# Main_Board_Guitar_Buffer.net
KiCad netlist of a schematic drawn in Altium Designer
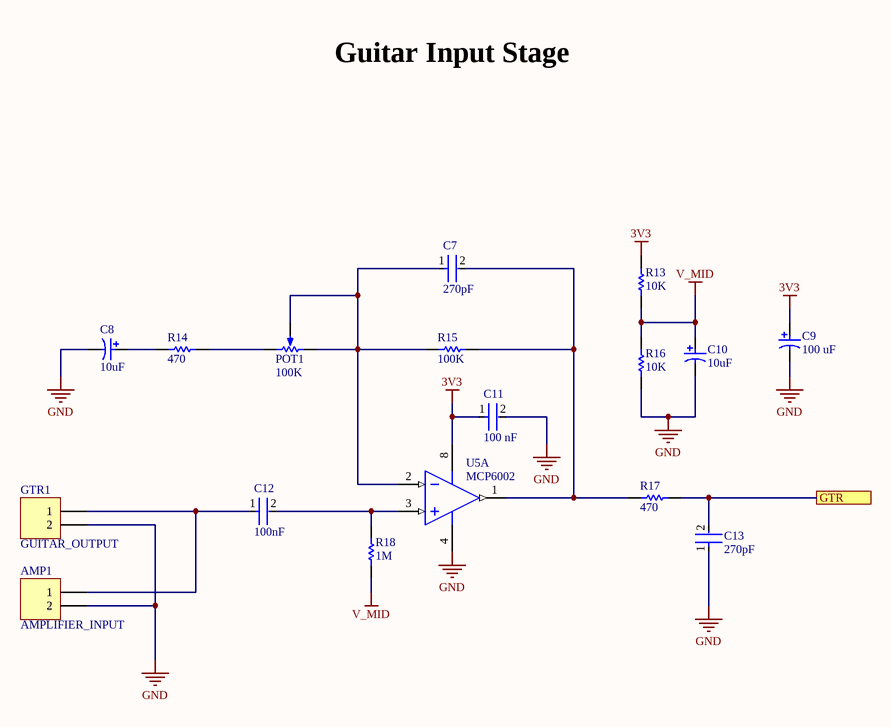
[diagram p0: Main_Board_Guitar_Buffer.SchDoc]

(export (version "E")
  (design (tool "Eeschema 10.0.6"))
  (components
    (comp (ref "AMP1")
      (value "AMPLIFIER_INPUT")
      (footprint "HDR1X2")
      (description "Header, 2-Pin")
      (fields (field (name "PUBLISHER") "Altium Limited"))
      (libsource (lib "Miscellaneous Connectors") (part "Header 2"))
    )
    (comp (ref "C7")
      (value "270pF")
      (footprint "FP-C0805C-DN-MFG")
      (description "CAP CER 270PF 50V C0G/NP0 0805")
      (fields
        (field (name "MANUFACTURER") "KEMET")
        (field (name "MANUFACTURER PART NUMBER") "C0805C271J5GACTU")
      )
      (libsource (lib "Altium Content Vault") (part "b4654b650e69147ec39a6b967a45e02"))
    )
    (comp (ref "C8")
      (value "10uF")
      (footprint "KEMT-A-3216-18-2_M")
      (description "Capacitor, Tantalum, 10 uF, +/- 10%, 10 V, -55 to 125 degC, 2-Pin SMD (1206), RoHS, Tape and Reel")
      (fields (field (name "TOLERANCE") "±10%") (field (name "MANUFACTURER") "Kemet"))
      (libsource (lib "Altium Content Vault") (part "CAP-P-2"))
    )
    (comp (ref "C9")
      (value "100 uF")
      (footprint "KEMT-T491-D_L")
      (fields
        (field (name "MANUFACTURER") "Kemet")
        (field (name "VOLTAGE") "16V")
        (field (name "TOLERANCE") "10%")
      )
      (libsource (lib "Altium Content Vault") (part "CAP-P-2"))
    )
    (comp (ref "C10")
      (value "10uF")
      (footprint "KEMT-A-3216-18-2_M")
      (description "Capacitor, Tantalum, 10 uF, +/- 10%, 10 V, -55 to 125 degC, 2-Pin SMD (1206), RoHS, Tape and Reel")
      (fields (field (name "TOLERANCE") "±10%") (field (name "MANUFACTURER") "Kemet"))
      (libsource (lib "Altium Content Vault") (part "CAP-P-2"))
    )
    (comp (ref "C11")
      (value "100 nF")
      (footprint "FP-C0805C-DN-MFG")
      (description "CAP CER 0.1UF 50V X7R 0805")
      (fields
        (field (name "MANUFACTURER PART NUMBER") "C0805C104K5RACTU")
        (field (name "MANUFACTURER") "KEMET")
      )
      (libsource (lib "Altium Content Vault") (part "b4654b650e69147ec39a6b967a45e02"))
    )
    (comp (ref "C12")
      (value "100nF")
      (footprint "FP-C0805C-DN-MFG")
      (description "CAP CER 0.1UF 50V X7R 0805")
      (fields
        (field (name "MANUFACTURER PART NUMBER") "C0805C104K5RACTU")
        (field (name "MANUFACTURER") "KEMET")
      )
      (libsource (lib "Altium Content Vault") (part "b4654b650e69147ec39a6b967a45e02"))
    )
    (comp (ref "C13")
      (value "270pF")
      (footprint "FP-C0805C-DN-MFG")
      (description "CAP CER 270PF 50V C0G/NP0 0805")
      (fields
        (field (name "MANUFACTURER") "KEMET")
        (field (name "MANUFACTURER PART NUMBER") "C0805C271J5GACTU")
      )
      (libsource (lib "Altium Content Vault") (part "b4654b650e69147ec39a6b967a45e02"))
    )
    (comp (ref "GTR1")
      (value "GUITAR_OUTPUT")
      (footprint "HDR1X2")
      (description "Header, 2-Pin")
      (fields (field (name "PUBLISHER") "Altium Limited"))
      (libsource (lib "Miscellaneous Connectors") (part "Header 2"))
    )
    (comp (ref "POT1")
      (value "100K")
      (footprint "BOUR-3362P")
      (description "Square Trimpot(R) Trimming Potentiometer, 100 KOhm, 300 V, -55 to 125 degC, 3-Pin THD, RoHS, Tube")
      (fields (field (name "TOLERANCE") "1%"))
      (libsource (lib "Altium Content Vault") (part "RES-POT-3"))
    )
    (comp (ref "R13")
      (value "10K")
      (footprint "RESC2013X60X35NL10T20")
      (description "Chip Resistor, 10 KOhm, +/- 1%, 0.125 W, -55 to 155 degC, 0805 (2012 Metric), RoHS, Tape and Reel")
      (fields (field (name "MANUFACTURER") "Yageo"))
      (libsource (lib "Altium Content Vault") (part "RES-2"))
    )
    (comp (ref "R14")
      (value "470")
      (footprint "RESC2013X70X40ML20T20")
      (description "Chip Resistor, 470 Ohm, +/- 1%, 0.125 W, -55 to 155 degC, 0805 (2012 Metric), RoHS, Tape and Reel")
      (fields (field (name "MANUFACTURER") "Panasonic"))
      (libsource (lib "Altium Content Vault") (part "RES-2"))
    )
    (comp (ref "R15")
      (value "100K")
      (footprint "RESC2013X60X35ML10T20")
      (description "Chip Resistor, 100 KOhm, +/- 1%, 0.125 W, -55 to 155 degC, 0805 (2012 Metric), RoHS, Tape and Reel")
      (fields (field (name "MANUFACTURER") "Yageo") (field (name "TOLERANCE") "1%"))
      (libsource (lib "Altium Content Vault") (part "RES-2"))
    )
    (comp (ref "R16")
      (value "10K")
      (footprint "RESC2013X60X35NL10T20")
      (description "Chip Resistor, 10 KOhm, +/- 1%, 0.125 W, -55 to 155 degC, 0805 (2012 Metric), RoHS, Tape and Reel")
      (fields (field (name "MANUFACTURER") "Yageo"))
      (libsource (lib "Altium Content Vault") (part "RES-2"))
    )
    (comp (ref "R17")
      (value "470")
      (footprint "RESC2013X70X40ML20T20")
      (description "Chip Resistor, 470 Ohm, +/- 1%, 0.125 W, -55 to 155 degC, 0805 (2012 Metric), RoHS, Tape and Reel")
      (fields (field (name "MANUFACTURER") "Panasonic"))
      (libsource (lib "Altium Content Vault") (part "RES-2"))
    )
    (comp (ref "R18")
      (value "1M")
      (footprint "RESC2013X70X40NL20T20")
      (fields (field (name "MANUFACTURER") "Panasonic"))
      (libsource (lib "Altium Content Vault") (part "RES-2"))
    )
    (comp (ref "U5")
      (value "MCP6002")
      (footprint "SOIC-SN8_M")
      (description "1 MHz, Low-Power Operational Amplifier, 8-Pin SOIC, Extended Temperature")
      (libsource (lib "Altium Content Vault") (part "AMP-OPA-MCP6002-IL8"))
    )
  )
  (nets
    (net (code "1") (name "/GTR") (class "Default")
      (node (ref "C13") (pin "2") (pinfunction "2_2") (pintype "passive"))
      (node (ref "R17") (pin "2") (pinfunction "2_2") (pintype "passive"))
    )
    (net (code "2") (name "3V3") (class "Default")
      (node (ref "C11") (pin "1") (pinfunction "1_1") (pintype "passive"))
      (node (ref "C9") (pin "1") (pinfunction "1_1") (pintype "passive"))
      (node (ref "R13") (pin "2") (pinfunction "2_2") (pintype "passive"))
      (node (ref "U5") (pin "8") (pinfunction "VDD_8") (pintype "power_in"))
    )
    (net (code "3") (name "GND") (class "Default")
      (node (ref "AMP1") (pin "2") (pinfunction "2_2") (pintype "passive"))
      (node (ref "C10") (pin "2") (pinfunction "2_2") (pintype "passive"))
      (node (ref "C11") (pin "2") (pinfunction "2_2") (pintype "passive"))
      (node (ref "C13") (pin "1") (pinfunction "1_1") (pintype "passive"))
      (node (ref "C8") (pin "2") (pinfunction "2_2") (pintype "passive"))
      (node (ref "C9") (pin "2") (pinfunction "2_2") (pintype "passive"))
      (node (ref "GTR1") (pin "2") (pinfunction "2_2") (pintype "passive"))
      (node (ref "R16") (pin "1") (pinfunction "1_1") (pintype "passive"))
      (node (ref "U5") (pin "4") (pinfunction "VSS_4") (pintype "power_in"))
    )
    (net (code "4") (name "Net-(AMP1-Pad1)") (class "Default")
      (node (ref "AMP1") (pin "1") (pinfunction "1_1") (pintype "passive"))
      (node (ref "C12") (pin "1") (pinfunction "1_1") (pintype "passive"))
      (node (ref "GTR1") (pin "1") (pinfunction "1_1") (pintype "passive"))
    )
    (net (code "5") (name "Net-(C8-Pad1)") (class "Default")
      (node (ref "C8") (pin "1") (pinfunction "1_1") (pintype "passive"))
      (node (ref "R14") (pin "1") (pinfunction "1_1") (pintype "passive"))
    )
    (net (code "6") (name "Net-(POT1-CCW)") (class "Default")
      (node (ref "C7") (pin "1") (pinfunction "1_1") (pintype "passive"))
      (node (ref "POT1") (pin "1") (pinfunction "CCW_1") (pintype "passive"))
      (node (ref "POT1") (pin "2") (pinfunction "S_2") (pintype "passive"))
      (node (ref "R15") (pin "1") (pinfunction "1_1") (pintype "passive"))
      (node (ref "U5") (pin "2") (pinfunction "VINA-_2") (pintype "input"))
    )
    (net (code "7") (name "Net-(POT1-CW)") (class "Default")
      (node (ref "POT1") (pin "3") (pinfunction "CW_3") (pintype "passive"))
      (node (ref "R14") (pin "2") (pinfunction "2_2") (pintype "passive"))
    )
    (net (code "8") (name "Net-(U5A-VINA+)") (class "Default")
      (node (ref "C12") (pin "2") (pinfunction "2_2") (pintype "passive"))
      (node (ref "R18") (pin "2") (pinfunction "2_2") (pintype "passive"))
      (node (ref "U5") (pin "3") (pinfunction "VINA+_3") (pintype "input"))
    )
    (net (code "9") (name "Net-(U5A-VOUTA)") (class "Default")
      (node (ref "C7") (pin "2") (pinfunction "2_2") (pintype "passive"))
      (node (ref "R15") (pin "2") (pinfunction "2_2") (pintype "passive"))
      (node (ref "R17") (pin "1") (pinfunction "1_1") (pintype "passive"))
      (node (ref "U5") (pin "1") (pinfunction "VOUTA_1") (pintype "output"))
    )
    (net (code "10") (name "V_MID") (class "Default")
      (node (ref "C10") (pin "1") (pinfunction "1_1") (pintype "passive"))
      (node (ref "R13") (pin "1") (pinfunction "1_1") (pintype "passive"))
      (node (ref "R16") (pin "2") (pinfunction "2_2") (pintype "passive"))
      (node (ref "R18") (pin "1") (pinfunction "1_1") (pintype "passive"))
    )
  )
)
